# Interfaces.net
KiCad netlist of a schematic drawn in Altium Designer
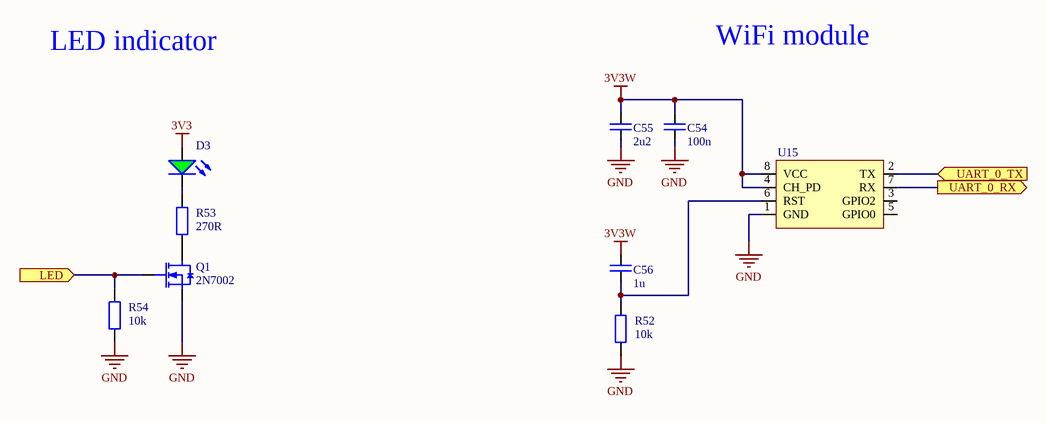
[diagram p0: Interfaces.SchDoc]

(export (version "E")
  (design (tool "Eeschema 10.0.6"))
  (components
    (comp (ref "C54")
      (value "100n")
      (footprint "C_0603")
      (description "Generic capacitor")
      (libsource (lib "DAQ") (part "Capacitor"))
    )
    (comp (ref "C55")
      (value "2u2")
      (footprint "C_0603")
      (description "Generic capacitor")
      (libsource (lib "DAQ") (part "Capacitor"))
    )
    (comp (ref "C56")
      (value "1u")
      (footprint "C_0603")
      (description "Generic capacitor")
      (libsource (lib "DAQ") (part "Capacitor"))
    )
    (comp (ref "D3")
      (value "LED Green")
      (footprint "LED_0603")
      (description "Generic LED Green")
      (libsource (lib "DAQ") (part "LED Green"))
    )
    (comp (ref "Q1")
      (value "2N7002")
      (footprint "SOT23-3")
      (description "60V 0.3A N-channel MOSFET")
      (fields (field (name "PART NUMBER") "XMN0002") (field (name "MANUFACTURER") "NXP"))
      (libsource (lib "DAQ") (part "2N7002"))
    )
    (comp (ref "R52")
      (value "10k")
      (footprint "R_0603")
      (description "Generic resistor")
      (fields (field (name "Comment") "comment"))
      (libsource (lib "DAQ") (part "Resistor"))
    )
    (comp (ref "R53")
      (value "270R")
      (footprint "R_0603")
      (description "Generic resistor")
      (fields (field (name "Comment") "comment"))
      (libsource (lib "DAQ") (part "Resistor"))
    )
    (comp (ref "R54")
      (value "10k")
      (footprint "R_0603")
      (description "Generic resistor")
      (fields (field (name "Comment") "comment"))
      (libsource (lib "DAQ") (part "Resistor"))
    )
    (comp (ref "U15")
      (value "ESP-01")
      (footprint "ESP-01")
      (description "WIFI module")
      (fields (field (name "PART NUMBER") "XWM0000"))
      (libsource (lib "DAQ") (part "ESP-01"))
    )
  )
  (nets
    (net (code "1") (name "/LED") (class "Default")
      (node (ref "Q1") (pin "1") (pinfunction "G_1") (pintype "passive"))
      (node (ref "R54") (pin "2") (pintype "passive"))
    )
    (net (code "2") (name "/UART_0_RX") (class "Default")
      (node (ref "U15") (pin "7") (pinfunction "RX_7") (pintype "passive"))
    )
    (net (code "3") (name "/UART_0_TX") (class "Default")
      (node (ref "U15") (pin "2") (pinfunction "TX_2") (pintype "passive"))
    )
    (net (code "4") (name "3V3") (class "Default")
      (node (ref "D3") (pin "2") (pinfunction "+_2") (pintype "passive"))
    )
    (net (code "5") (name "3V3W") (class "Default")
      (node (ref "C54") (pin "2") (pinfunction "2_2") (pintype "passive"))
      (node (ref "C55") (pin "2") (pinfunction "2_2") (pintype "passive"))
      (node (ref "C56") (pin "2") (pinfunction "2_2") (pintype "passive"))
      (node (ref "U15") (pin "4") (pinfunction "CH_PD_4") (pintype "passive"))
      (node (ref "U15") (pin "8") (pinfunction "VCC_8") (pintype "passive"))
    )
    (net (code "6") (name "GND") (class "Default")
      (node (ref "C54") (pin "1") (pinfunction "1_1") (pintype "passive"))
      (node (ref "C55") (pin "1") (pinfunction "1_1") (pintype "passive"))
      (node (ref "Q1") (pin "2") (pinfunction "S_2") (pintype "passive"))
      (node (ref "R52") (pin "1") (pintype "passive"))
      (node (ref "R54") (pin "1") (pintype "passive"))
      (node (ref "U15") (pin "1") (pinfunction "GND_1") (pintype "passive"))
    )
    (net (code "7") (name "Net-(D3--)") (class "Default")
      (node (ref "D3") (pin "1") (pinfunction "-_1") (pintype "passive"))
      (node (ref "R53") (pin "2") (pintype "passive"))
    )
    (net (code "8") (name "Net-(Q1-D)") (class "Default")
      (node (ref "Q1") (pin "3") (pinfunction "D_3") (pintype "passive"))
      (node (ref "R53") (pin "1") (pintype "passive"))
    )
    (net (code "9") (name "Net-(U15-RST)") (class "Default")
      (node (ref "C56") (pin "1") (pinfunction "1_1") (pintype "passive"))
      (node (ref "R52") (pin "2") (pintype "passive"))
      (node (ref "U15") (pin "6") (pinfunction "RST_6") (pintype "passive"))
    )
    (net (code "10") (name "unconnected-(U15-GPIO0-Pad5)") (class "Default")
      (node (ref "U15") (pin "5") (pinfunction "GPIO0_5") (pintype "passive"))
    )
    (net (code "11") (name "unconnected-(U15-GPIO2-Pad3)") (class "Default")
      (node (ref "U15") (pin "3") (pinfunction "GPIO2_3") (pintype "passive"))
    )
  )
)
